# SEP00000AG.net
KiCad netlist of a schematic drawn in Altium Designer
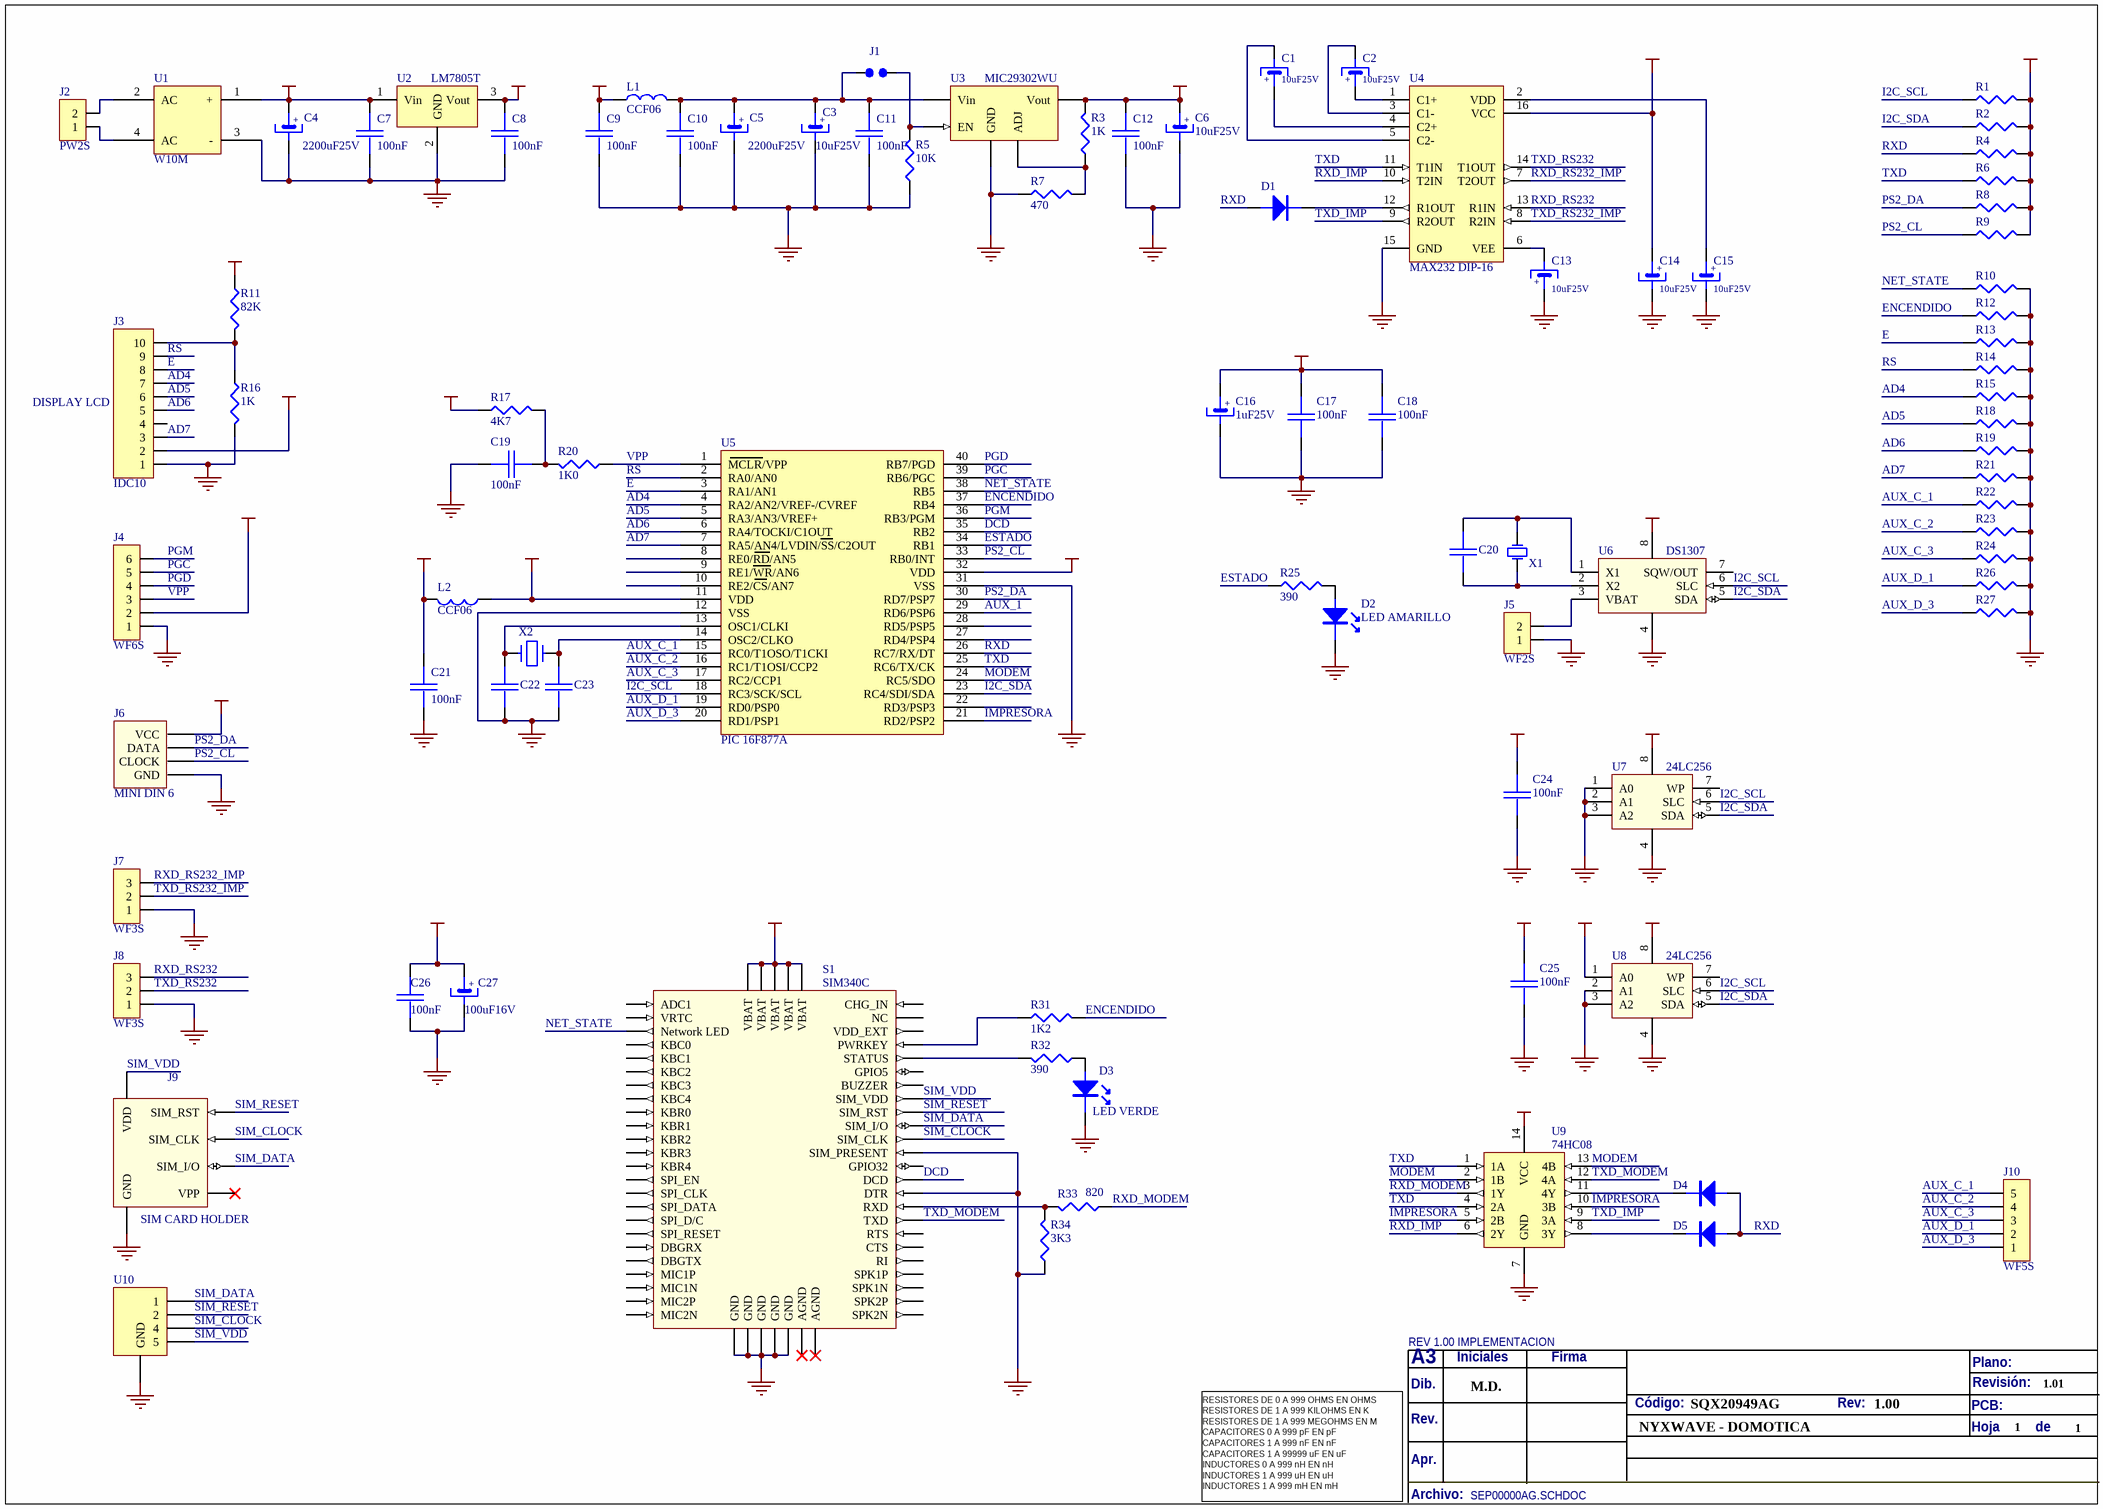
[diagram p0: SEP00000AG.SCHDOC]

(export (version "E")
  (design (tool "Eeschema 10.0.6"))
  (components
    (comp (ref "C1")
      (value "10uF25V")
      (footprint "CE 2.0/5.0")
      (description "CAPACITOR ELECTROLITICO RADIAL 5X11mm PASO 2mm 85ªC +/-20 25V 10uF")
      (libsource (lib "CAPACITORES ELECTROLITICOS") (part "10uF25V 5X11X2"))
    )
    (comp (ref "C2")
      (value "10uF25V")
      (footprint "CE 2.0/5.0")
      (description "CAPACITOR ELECTROLITICO RADIAL 5X11mm PASO 2mm 85ªC +/-20 25V 10uF")
      (libsource (lib "CAPACITORES ELECTROLITICOS") (part "10uF25V 5X11X2"))
    )
    (comp (ref "C3")
      (value "10uF25V")
      (footprint "CE 1.5/4.0")
      (description "CAPACITOR ELECTROLITICO RADIAL 5X7mm PASO 1.5mm 85ªC +/-20 25V 10uF")
      (libsource (lib "CAPACITORES ELECTROLITICOS") (part "10uF25V 4X7X1.5"))
    )
    (comp (ref "C4")
      (value "2200uF25V")
      (footprint "CE 5.0/12.5")
      (description "CAPACITOR ELECTROLITICO RADIAL 12.5X26 mm PASO 5 mm +/-20% 85ºC 25V 2200uF")
      (libsource (lib "CAPACITORES ELECTROLITICOS") (part "2200uF25V"))
    )
    (comp (ref "C5")
      (value "2200uF25V")
      (footprint "CE 5.0/12.5")
      (description "CAPACITOR ELECTROLITICO RADIAL 12.5X26 mm PASO 5 mm +/-20% 85ºC 25V 2200uF")
      (libsource (lib "CAPACITORES ELECTROLITICOS") (part "2200uF25V"))
    )
    (comp (ref "C6")
      (value "10uF25V")
      (footprint "CE 1.5/4.0")
      (description "CAPACITOR ELECTROLITICO RADIAL 5X7mm PASO 1.5mm 85ªC +/-20 25V 10uF")
      (libsource (lib "CAPACITORES ELECTROLITICOS") (part "10uF25V 4X7X1.5"))
    )
    (comp (ref "C7")
      (value "100nF")
      (footprint "0805")
      (description "CAPACITOR SMD 0805 X7R  50 V 100 nF")
      (libsource (lib "CAPACITORES SMD0805") (part "100n"))
    )
    (comp (ref "C8")
      (value "100nF")
      (footprint "0805")
      (description "CAPACITOR SMD 0805 X7R  50 V 100 nF")
      (libsource (lib "CAPACITORES SMD0805") (part "100n"))
    )
    (comp (ref "C9")
      (value "100nF")
      (footprint "0805")
      (description "CAPACITOR SMD 0805 X7R  50 V 100 nF")
      (libsource (lib "CAPACITORES SMD0805") (part "100n"))
    )
    (comp (ref "C10")
      (value "100nF")
      (footprint "0805")
      (description "CAPACITOR SMD 0805 X7R  50 V 100 nF")
      (libsource (lib "CAPACITORES SMD0805") (part "100n"))
    )
    (comp (ref "C11")
      (value "100nF")
      (footprint "0805")
      (description "CAPACITOR SMD 0805 X7R  50 V 100 nF")
      (libsource (lib "CAPACITORES SMD0805") (part "100n"))
    )
    (comp (ref "C12")
      (value "100nF")
      (footprint "0805")
      (description "CAPACITOR SMD 0805 X7R  50 V 100 nF")
      (libsource (lib "CAPACITORES SMD0805") (part "100n"))
    )
    (comp (ref "C13")
      (value "10uF25V")
      (footprint "CE 2.0/5.0")
      (description "CAPACITOR ELECTROLITICO RADIAL 5X11mm PASO 2mm 85ªC +/-20 25V 10uF")
      (libsource (lib "CAPACITORES ELECTROLITICOS") (part "10uF25V 5X11X2"))
    )
    (comp (ref "C14")
      (value "10uF25V")
      (footprint "CE 2.0/5.0")
      (description "CAPACITOR ELECTROLITICO RADIAL 5X11mm PASO 2mm 85ªC +/-20 25V 10uF")
      (libsource (lib "CAPACITORES ELECTROLITICOS") (part "10uF25V 5X11X2"))
    )
    (comp (ref "C15")
      (value "10uF25V")
      (footprint "CE 2.0/5.0")
      (description "CAPACITOR ELECTROLITICO RADIAL 5X11mm PASO 2mm 85ªC +/-20 25V 10uF")
      (libsource (lib "CAPACITORES ELECTROLITICOS") (part "10uF25V 5X11X2"))
    )
    (comp (ref "C16")
      (value "1uF25V")
      (footprint "CE 2.5/5.0")
      (description "CAP ELECT RAD 1.0UF 25V 5X11MM PASO 2MM 85ºC")
      (libsource (lib "CAPACITORES ELECTROLITICOS") (part "1uF25V"))
    )
    (comp (ref "C17")
      (value "100nF")
      (footprint "0805")
      (description "CAPACITOR SMD 0805 X7R  50 V 100 nF")
      (libsource (lib "CAPACITORES SMD0805") (part "100n"))
    )
    (comp (ref "C18")
      (value "100nF")
      (footprint "0805")
      (description "CAPACITOR SMD 0805 X7R  50 V 100 nF")
      (libsource (lib "CAPACITORES SMD0805") (part "100n"))
    )
    (comp (ref "C19")
      (value "100nF")
      (footprint "0805")
      (description "CAPACITOR SMD 0805 X7R  50 V 100 nF")
      (libsource (lib "CAPACITORES SMD0805") (part "100n"))
    )
    (comp (ref "C20")
      (value "15p")
      (footprint "CAP2.54")
      (description "CAPACITOR CERAMICO DISCO 2.54 mm  X7R  50V  15pF")
      (libsource (lib "CAPACITORES CERAMICO DISCO") (part "15p"))
    )
    (comp (ref "C21")
      (value "100nF")
      (footprint "0805")
      (description "CAPACITOR SMD 0805 X7R  50 V 100 nF")
      (libsource (lib "CAPACITORES SMD0805") (part "100n"))
    )
    (comp (ref "C22")
      (value "15p")
      (footprint "CAP2.54")
      (description "CAPACITOR CERAMICO DISCO 2.54 mm  X7R  50V  15pF")
      (libsource (lib "CAPACITORES CERAMICO DISCO") (part "15p"))
    )
    (comp (ref "C23")
      (value "15p")
      (footprint "CAP2.54")
      (description "CAPACITOR CERAMICO DISCO 2.54 mm  X7R  50V  15pF")
      (libsource (lib "CAPACITORES CERAMICO DISCO") (part "15p"))
    )
    (comp (ref "C24")
      (value "100nF")
      (footprint "0805")
      (description "CAPACITOR SMD 0805 X7R  50 V 100 nF")
      (libsource (lib "CAPACITORES SMD0805") (part "100n"))
    )
    (comp (ref "C25")
      (value "100nF")
      (footprint "0805")
      (description "CAPACITOR SMD 0805 X7R  50 V 100 nF")
      (libsource (lib "CAPACITORES SMD0805") (part "100n"))
    )
    (comp (ref "C26")
      (value "100nF")
      (footprint "0805")
      (description "CAPACITOR SMD 0805 X7R  50 V 100 nF")
      (libsource (lib "CAPACITORES SMD0805") (part "100n"))
    )
    (comp (ref "C27")
      (value "100uF16V")
      (footprint "CE 3.5/8.0")
      (description "CAP ELECT RADIAL 100UF 16V 6.3X12MM PASO 2.5MM 85ºC 20%")
      (libsource (lib "CAPACITORES ELECTROLITICOS") (part "100uF16V"))
    )
    (comp (ref "D1")
      (value "1N4148 DO-35")
      (footprint "DO-35_200")
      (description "1N4148 DO-35 DIODO")
      (libsource (lib "DIODOS") (part "1N4148 DO-35"))
    )
    (comp (ref "D2")
      (value "LED AMARILLO")
      (footprint "LED 3MM")
      (description "LED AMARILLO 3MM")
      (libsource (lib "DIODOS") (part "LED AMARILLO 3MM"))
    )
    (comp (ref "D3")
      (value "LED VERDE")
      (footprint "LED 3MM")
      (description "LED VERDE 3MM")
      (libsource (lib "DIODOS") (part "LED VERDE 3MM"))
    )
    (comp (ref "D4")
      (value "1N4148 DO-35")
      (footprint "DO-35_200")
      (description "1N4148 DO-35 DIODO")
      (libsource (lib "DIODOS") (part "1N4148 DO-35"))
    )
    (comp (ref "D5")
      (value "1N4148 DO-35")
      (footprint "DO-35_200")
      (description "1N4148 DO-35 DIODO")
      (libsource (lib "DIODOS") (part "1N4148 DO-35"))
    )
    (comp (ref "J1") (value "Jumper") (footprint "IDC2") (libsource (lib "CONECTORES") (part "Jumper")))
    (comp (ref "J2")
      (value "PW2S")
      (footprint "PW2S")
      (description "PW2S HEADER .156\" RECTO 2 VIAS")
      (libsource (lib "CONECTORES") (part "PW2S"))
    )
    (comp (ref "J3")
      (value "IDC10")
      (footprint "IDC10")
      (description "CONECTOR IDC HEMBRA PCB NO POLARIZADO PASO 2.54 mm RECTO 2X5 VIAS")
      (libsource (lib "CONECTORES") (part "IDC10"))
    )
    (comp (ref "J4")
      (value "WF6S")
      (footprint "WF6S")
      (description "WF6S CONECTOR MACHO PASO 2.54 MM  6 VIAS RECTO")
      (libsource (lib "CONECTORES") (part "WF6S"))
    )
    (comp (ref "J5")
      (value "WF2S")
      (footprint "WF2S")
      (description "WF2S HEADER .100\" RECTO 2 VIAS")
      (libsource (lib "CONECTORES") (part "WF2S"))
    )
    (comp (ref "J6")
      (value "MINI DIN 6")
      (footprint "MINI DIN PCB")
      (description "CONECTOR MINI DIN 6 PARA PCB")
      (libsource (lib "mini din") (part "CONECTOR MINI DIN 6"))
    )
    (comp (ref "J7")
      (value "WF3S")
      (footprint "WF3S")
      (description "WF3S HEADER .100\" RECTO 3 VIAS")
      (libsource (lib "CONECTORES") (part "WF3S"))
    )
    (comp (ref "J8")
      (value "WF3S")
      (footprint "WF3S")
      (description "WF3S HEADER .100\" RECTO 3 VIAS")
      (libsource (lib "CONECTORES") (part "WF3S"))
    )
    (comp (ref "J9")
      (value "SIM CARD HOLDER")
      (footprint "SIM CARD HOLDER")
      (description "ZOCALO PARA TARJETA DE MEMORIA SIM")
      (libsource (lib "CONECTORES") (part "SIM CARD HOLDER"))
    )
    (comp (ref "J10")
      (value "WF5S")
      (footprint "WF5S")
      (description "WF5S HEADER .100\" RECTO 5 VIAS")
      (libsource (lib "CONECTORES") (part "WF5S"))
    )
    (comp (ref "L1")
      (value "CCF06")
      (footprint "AXIAL10X4_300")
      (description "INDUCTOR CCF06")
      (libsource (lib "INDUCTORES") (part "CCF06"))
    )
    (comp (ref "L2")
      (value "CCF06")
      (footprint "AXIAL10X4_300")
      (description "INDUCTOR CCF06")
      (libsource (lib "INDUCTORES") (part "CCF06"))
    )
    (comp (ref "R1")
      (value "10K")
      (footprint "0805")
      (description "RESISTOR SMD0805 0.125 W 5%  10 K OHMS")
      (libsource (lib "RESISTORES SMD0805") (part "10K"))
    )
    (comp (ref "R2")
      (value "10K")
      (footprint "0805")
      (description "RESISTOR SMD0805 0.125 W 5%  10 K OHMS")
      (libsource (lib "RESISTORES SMD0805") (part "10K"))
    )
    (comp (ref "R3")
      (value "1K")
      (footprint "RES_MF1/2W_200")
      (description "RESISTOR METAL FILM 0.5 W 5% 1 K OHMS")
      (libsource (lib "RESISTORES METAL FILM MEDIO WATT") (part "1K"))
    )
    (comp (ref "R4")
      (value "100K")
      (footprint "0805")
      (description "RESISTOR SMD0805 0.125 W 5%  100 K OHMS")
      (libsource (lib "RESISTORES SMD0805") (part "100K"))
    )
    (comp (ref "R5")
      (value "10K")
      (footprint "0805")
      (description "RESISTOR SMD0805 0.125 W 5%  10 K OHMS")
      (libsource (lib "RESISTORES SMD0805") (part "10K"))
    )
    (comp (ref "R6")
      (value "100K")
      (footprint "0805")
      (description "RESISTOR SMD0805 0.125 W 5%  100 K OHMS")
      (libsource (lib "RESISTORES SMD0805") (part "100K"))
    )
    (comp (ref "R7")
      (value "470")
      (footprint "RES_MF1/2W_200")
      (description "RESISTOR METAL FILM 0.5 W 5% 470 OHMS")
      (libsource (lib "RESISTORES METAL FILM MEDIO WATT") (part "470"))
    )
    (comp (ref "R8")
      (value "5K6")
      (footprint "0805")
      (description "RESISTOR SMD0805 0.125 W 5%  5.6 K OHMS")
      (libsource (lib "RESISTORES SMD0805") (part "5K6"))
    )
    (comp (ref "R9")
      (value "5K6")
      (footprint "0805")
      (description "RESISTOR SMD0805 0.125 W 5%  5.6 K OHMS")
      (libsource (lib "RESISTORES SMD0805") (part "5K6"))
    )
    (comp (ref "R10")
      (value "5K6")
      (footprint "0805")
      (description "RESISTOR SMD0805 0.125 W 5%  5.6 K OHMS")
      (libsource (lib "RESISTORES SMD0805") (part "5K6"))
    )
    (comp (ref "R11")
      (value "82K")
      (footprint "RES_MF1/2W_200")
      (description "RESISTOR METAL FILM 0.5 W 5% 82 KILOHMS")
      (libsource (lib "RESISTORES METAL FILM MEDIO WATT") (part "82K"))
    )
    (comp (ref "R12")
      (value "5K6")
      (footprint "0805")
      (description "RESISTOR SMD0805 0.125 W 5%  5.6 K OHMS")
      (libsource (lib "RESISTORES SMD0805") (part "5K6"))
    )
    (comp (ref "R13")
      (value "5K6")
      (footprint "0805")
      (description "RESISTOR SMD0805 0.125 W 5%  5.6 K OHMS")
      (libsource (lib "RESISTORES SMD0805") (part "5K6"))
    )
    (comp (ref "R14")
      (value "5K6")
      (footprint "0805")
      (description "RESISTOR SMD0805 0.125 W 5%  5.6 K OHMS")
      (libsource (lib "RESISTORES SMD0805") (part "5K6"))
    )
    (comp (ref "R15")
      (value "5K6")
      (footprint "0805")
      (description "RESISTOR SMD0805 0.125 W 5%  5.6 K OHMS")
      (libsource (lib "RESISTORES SMD0805") (part "5K6"))
    )
    (comp (ref "R16")
      (value "1K")
      (footprint "RES_MF1/2W_200")
      (description "RESISTOR METAL FILM 0.5 W 5% 1 K OHMS")
      (libsource (lib "RESISTORES METAL FILM MEDIO WATT") (part "1K"))
    )
    (comp (ref "R17")
      (value "4K7")
      (footprint "RES_MF1/2W_200")
      (description "RESISTOR METAL FILM 0.5 W 5% 4.7 KILOHMS")
      (libsource (lib "RESISTORES METAL FILM MEDIO WATT") (part "4K7"))
    )
    (comp (ref "R18")
      (value "5K6")
      (footprint "0805")
      (description "RESISTOR SMD0805 0.125 W 5%  5.6 K OHMS")
      (libsource (lib "RESISTORES SMD0805") (part "5K6"))
    )
    (comp (ref "R19")
      (value "5K6")
      (footprint "0805")
      (description "RESISTOR SMD0805 0.125 W 5%  5.6 K OHMS")
      (libsource (lib "RESISTORES SMD0805") (part "5K6"))
    )
    (comp (ref "R20")
      (value "1K0")
      (footprint "0805")
      (description "RESISTOR SMD0805 0.125 W 5%  1 K OHMS")
      (libsource (lib "RESISTORES SMD0805") (part "1K0"))
    )
    (comp (ref "R21")
      (value "5K6")
      (footprint "0805")
      (description "RESISTOR SMD0805 0.125 W 5%  5.6 K OHMS")
      (libsource (lib "RESISTORES SMD0805") (part "5K6"))
    )
    (comp (ref "R22")
      (value "8K2")
      (footprint "0805")
      (description "RESISTOR SMD0805 0.125 W 5%  8.2 K OHMS")
      (libsource (lib "RESISTORES SMD0805") (part "8K2"))
    )
    (comp (ref "R23")
      (value "8K2")
      (footprint "0805")
      (description "RESISTOR SMD0805 0.125 W 5%  8.2 K OHMS")
      (libsource (lib "RESISTORES SMD0805") (part "8K2"))
    )
    (comp (ref "R24")
      (value "8K2")
      (footprint "0805")
      (description "RESISTOR SMD0805 0.125 W 5%  8.2 K OHMS")
      (libsource (lib "RESISTORES SMD0805") (part "8K2"))
    )
    (comp (ref "R25")
      (value "390")
      (footprint "RES_MF1/2W_200")
      (description "RESISTOR METAL FILM 0.5 W 5% 390 OHMS")
      (libsource (lib "RESISTORES METAL FILM MEDIO WATT") (part "390"))
    )
    (comp (ref "R26")
      (value "8K2")
      (footprint "0805")
      (description "RESISTOR SMD0805 0.125 W 5%  8.2 K OHMS")
      (libsource (lib "RESISTORES SMD0805") (part "8K2"))
    )
    (comp (ref "R27")
      (value "8K2")
      (footprint "0805")
      (description "RESISTOR SMD0805 0.125 W 5%  8.2 K OHMS")
      (libsource (lib "RESISTORES SMD0805") (part "8K2"))
    )
    (comp (ref "R31")
      (value "1K2")
      (footprint "0805")
      (description "RESISTOR SMD0805 0.125 W 5%  1.2 K OHMS")
      (libsource (lib "RESISTORES SMD0805") (part "1K2"))
    )
    (comp (ref "R32")
      (value "390")
      (footprint "RES_MF1/2W_200")
      (description "RESISTOR METAL FILM 0.5 W 5% 390 OHMS")
      (libsource (lib "RESISTORES METAL FILM MEDIO WATT") (part "390"))
    )
    (comp (ref "R33")
      (value "820")
      (footprint "RES_MF1/2W_200")
      (description "RESISTOR METAL FILM 0.5 W 5% 820 OHMS")
      (libsource (lib "RESISTORES METAL FILM MEDIO WATT") (part "820"))
    )
    (comp (ref "R34")
      (value "3K3")
      (footprint "RES_MF1/2W_200")
      (description "RESISTOR METAL FILM 0.5 W 5% 3.3 KILOHMS")
      (libsource (lib "RESISTORES METAL FILM MEDIO WATT") (part "3K3"))
    )
    (comp (ref "S1")
      (value "SIM340C")
      (footprint "SIM340C")
      (description "SIM340C QUAD-BAND GSM/GPRS GSM850MHz/EGSM900MHz/DCS18000MHz/PCS1900MHz")
      (libsource (lib "SUBCONJUNTOS") (part "SIM340C QUAD-BAND GSM/GPRS"))
    )
    (comp (ref "U1")
      (value "W10M")
      (footprint "CASE22")
      (description "W10M CASE22 CIRC INT RECTIFICADOR PUENTE 1000V 1A")
      (libsource (lib "CIRCUITOS INTEGRADOS DIP") (part "W10M"))
    )
    (comp (ref "U2")
      (value "LM7805T")
      (footprint "TO-220_1")
      (description "LM7805T TO-220 CIRC INT")
      (libsource (lib "CIRCUITOS INTEGRADOS DIP") (part "LM7805T"))
    )
    (comp (ref "U3")
      (value "MIC29302WU")
      (footprint "TO-220-5S")
      (description "MIC29302WU TO-220 (T) HIGH CURRENT LOW DROPOUT REGULATORS")
      (libsource (lib "CIRCUITOS INTEGRADOS DIP") (part "MIC29302WU"))
    )
    (comp (ref "U4")
      (value "MAX232 DIP-16")
      (footprint "DIP16")
      (description "MAX232 DIP-16 CIRCUITO INTEGRADO")
      (libsource (lib "Maxim Communication Transceiver") (part "MAX232 DIP-16"))
    )
    (comp (ref "U5")
      (value "PIC 16F877A")
      (footprint "DIP40")
      (description "PIC16F877A-I/P DIP-40 MICROCHIP")
      (libsource (lib "CIRCUITOS INTEGRADOS DIP") (part "PIC 16F877A"))
    )
    (comp (ref "U6")
      (value "DS1307")
      (footprint "DIP8")
      (description "64 X 8 SERIAL REAL TIME CLOCK")
      (libsource (lib "CIRCUITOS INTEGRADOS DIP") (part "DS1307"))
    )
    (comp (ref "U7")
      (value "24LC256")
      (footprint "DIP8")
      (description "256K I2C CMOS Serial EEPROM")
      (libsource (lib "CIRCUITOS INTEGRADOS DIP") (part "24LC256"))
    )
    (comp (ref "U8")
      (value "24LC256")
      (footprint "DIP8")
      (description "256K I2C CMOS Serial EEPROM")
      (libsource (lib "CIRCUITOS INTEGRADOS DIP") (part "24LC256"))
    )
    (comp (ref "U9")
      (value "74HC08")
      (footprint "DIP14")
      (description "74HC08 DIP-14 QUAD 2-INPUT AND GATE")
      (libsource (lib "CIRCUITOS INTEGRADOS DIP") (part "74HC08 DIP"))
    )
    (comp (ref "U10")
      (value "ESDA6V1W5")
      (footprint "SOT-323-5L")
      (description "ESDA6V1W5 ARRAY  FOR ESD PROTECTION")
      (libsource (lib "CIRCUITOS INTEGRADOS SMD") (part "ESDA6V1W5"))
    )
    (comp (ref "X1")
      (value "XL20M-UM5")
      (footprint "UM5")
      (description "XL20M-UM5 CRISTAL DE 20 MHZ 10ppm")
      (libsource (lib "CRISTALES") (part "XL20M-UM5"))
    )
    (comp (ref "X2")
      (value "20MHz")
      (footprint "UM5")
      (description "20.000 MHZ XL20M-UM5 10PPM CRISTAL")
      (libsource (lib "*") (part "CRYSTAL"))
    )
  )
  (nets
    (net (code "1") (name "+5V") (class "Default")
      (node (ref "C14") (pin "1") (pinfunction "1_1") (pintype "passive"))
      (node (ref "C21") (pin "2") (pintype "passive"))
      (node (ref "C24") (pin "2") (pintype "passive"))
      (node (ref "C25") (pin "2") (pintype "passive"))
      (node (ref "C8") (pin "2") (pintype "passive"))
      (node (ref "J3") (pin "2") (pinfunction "2_2") (pintype "passive"))
      (node (ref "J6") (pin "4") (pinfunction "VCC_4") (pintype "power_in"))
      (node (ref "L2") (pin "2") (pintype "passive"))
      (node (ref "R1") (pin "2") (pintype "passive"))
      (node (ref "R11") (pin "2") (pintype "passive"))
      (node (ref "R17") (pin "1") (pintype "passive"))
      (node (ref "R2") (pin "2") (pintype "passive"))
      (node (ref "R4") (pin "2") (pintype "passive"))
      (node (ref "R6") (pin "2") (pintype "passive"))
      (node (ref "R8") (pin "2") (pintype "passive"))
      (node (ref "R9") (pin "2") (pintype "passive"))
      (node (ref "U2") (pin "3") (pinfunction "Vout_3") (pintype "passive"))
      (node (ref "U4") (pin "16") (pinfunction "VCC_16") (pintype "power_in"))
      (node (ref "U6") (pin "8") (pinfunction "VCC_8") (pintype "power_in"))
      (node (ref "U7") (pin "8") (pinfunction "VCC_8") (pintype "power_in"))
      (node (ref "U8") (pin "1") (pinfunction "A0_1") (pintype "passive"))
      (node (ref "U8") (pin "8") (pinfunction "VCC_8") (pintype "power_in"))
      (node (ref "U9") (pin "14") (pinfunction "VCC_14") (pintype "power_in"))
    )
    (net (code "5") (name "/AD4") (class "Default")
      (node (ref "J3") (pin "7") (pinfunction "7_7") (pintype "passive"))
      (node (ref "R15") (pin "1") (pintype "passive"))
      (node (ref "U5") (pin "4") (pinfunction "RA2/AN2/VREF-/CVREF_4") (pintype "passive"))
    )
    (net (code "6") (name "/AD5") (class "Default")
      (node (ref "J3") (pin "6") (pinfunction "6_6") (pintype "passive"))
      (node (ref "R18") (pin "1") (pintype "passive"))
      (node (ref "U5") (pin "5") (pinfunction "RA3/AN3/VREF+_5") (pintype "passive"))
    )
    (net (code "7") (name "/AD6") (class "Default")
      (node (ref "J3") (pin "5") (pinfunction "5_5") (pintype "passive"))
      (node (ref "R19") (pin "1") (pintype "passive"))
      (node (ref "U5") (pin "6") (pinfunction "RA4/TOCKI/C1OUT_6") (pintype "passive"))
    )
    (net (code "8") (name "/AD7") (class "Default")
      (node (ref "J3") (pin "3") (pinfunction "3_3") (pintype "passive"))
      (node (ref "R21") (pin "1") (pintype "passive"))
      (node (ref "U5") (pin "7") (pinfunction "RA5/AN4/LVDIN/SS/C2OUT_7") (pintype "passive"))
    )
    (net (code "9") (name "/AUX_1") (class "Default")
      (node (ref "U5") (pin "29") (pinfunction "RD6/PSP6_29") (pintype "passive"))
    )
    (net (code "10") (name "/AUX_C_1") (class "Default")
      (node (ref "J10") (pin "5") (pinfunction "5_5") (pintype "passive"))
      (node (ref "R22") (pin "1") (pintype "passive"))
      (node (ref "U5") (pin "15") (pinfunction "RC0/T1OSO/T1CKI_15") (pintype "passive"))
    )
    (net (code "11") (name "/AUX_C_2") (class "Default")
      (node (ref "J10") (pin "4") (pinfunction "4_4") (pintype "passive"))
      (node (ref "R23") (pin "1") (pintype "passive"))
      (node (ref "U5") (pin "16") (pinfunction "RC1/T1OSI/CCP2_16") (pintype "passive"))
    )
    (net (code "12") (name "/AUX_C_3") (class "Default")
      (node (ref "J10") (pin "3") (pinfunction "3_3") (pintype "passive"))
      (node (ref "R24") (pin "1") (pintype "passive"))
      (node (ref "U5") (pin "17") (pinfunction "RC2/CCP1_17") (pintype "passive"))
    )
    (net (code "13") (name "/AUX_D_1") (class "Default")
      (node (ref "J10") (pin "2") (pinfunction "2_2") (pintype "passive"))
      (node (ref "R26") (pin "1") (pintype "passive"))
      (node (ref "U5") (pin "19") (pinfunction "RD0/PSP0_19") (pintype "passive"))
    )
    (net (code "14") (name "/AUX_D_3") (class "Default")
      (node (ref "J10") (pin "1") (pinfunction "1_1") (pintype "passive"))
      (node (ref "R27") (pin "1") (pintype "passive"))
      (node (ref "U5") (pin "20") (pinfunction "RD1/PSP1_20") (pintype "passive"))
    )
    (net (code "15") (name "/DCD") (class "Default")
      (node (ref "S1") (pin "37") (pinfunction "DCD_37") (pintype "output"))
      (node (ref "U5") (pin "35") (pinfunction "RB2_35") (pintype "passive"))
    )
    (net (code "16") (name "/E") (class "Default")
      (node (ref "J3") (pin "8") (pinfunction "8_8") (pintype "passive"))
      (node (ref "R13") (pin "1") (pintype "passive"))
      (node (ref "U5") (pin "3") (pinfunction "RA1/AN1_3") (pintype "passive"))
    )
    (net (code "17") (name "/ENCENDIDO") (class "Default")
      (node (ref "R12") (pin "1") (pintype "passive"))
      (node (ref "R31") (pin "2") (pintype "passive"))
      (node (ref "U5") (pin "37") (pinfunction "RB4_37") (pintype "passive"))
    )
    (net (code "18") (name "/ESTADO") (class "Default")
      (node (ref "R25") (pin "1") (pintype "passive"))
      (node (ref "U5") (pin "34") (pinfunction "RB1_34") (pintype "passive"))
    )
    (net (code "19") (name "/I2C_SCL") (class "Default")
      (node (ref "R1") (pin "1") (pintype "passive"))
      (node (ref "U5") (pin "18") (pinfunction "RC3/SCK/SCL_18") (pintype "passive"))
      (node (ref "U6") (pin "6") (pinfunction "SLC_6") (pintype "input"))
      (node (ref "U7") (pin "6") (pinfunction "SLC_6") (pintype "input"))
      (node (ref "U8") (pin "6") (pinfunction "SLC_6") (pintype "input"))
    )
    (net (code "20") (name "/I2C_SDA") (class "Default")
      (node (ref "R2") (pin "1") (pintype "passive"))
      (node (ref "U5") (pin "23") (pinfunction "RC4/SDI/SDA_23") (pintype "passive"))
      (node (ref "U6") (pin "5") (pinfunction "SDA_5") (pintype "bidirectional"))
      (node (ref "U7") (pin "5") (pinfunction "SDA_5") (pintype "bidirectional"))
      (node (ref "U8") (pin "5") (pinfunction "SDA_5") (pintype "bidirectional"))
    )
    (net (code "21") (name "/IMPRESORA") (class "Default")
      (node (ref "U5") (pin "21") (pinfunction "RD2/PSP2_21") (pintype "passive"))
      (node (ref "U9") (pin "10") (pinfunction "3B_10") (pintype "input"))
      (node (ref "U9") (pin "5") (pinfunction "2B_5") (pintype "input"))
    )
    (net (code "23") (name "/MODEM") (class "Default")
      (node (ref "U5") (pin "24") (pinfunction "RC5/SDO_24") (pintype "passive"))
      (node (ref "U9") (pin "13") (pinfunction "4B_13") (pintype "input"))
      (node (ref "U9") (pin "2") (pinfunction "1B_2") (pintype "input"))
    )
    (net (code "24") (name "/NET_STATE") (class "Default")
      (node (ref "R10") (pin "1") (pintype "passive"))
      (node (ref "S1") (pin "16") (pinfunction "Network_LED_16") (pintype "output"))
      (node (ref "U5") (pin "38") (pinfunction "RB5_38") (pintype "passive"))
    )
    (net (code "26") (name "/PGC") (class "Default")
      (node (ref "J4") (pin "5") (pinfunction "5_5") (pintype "passive"))
      (node (ref "U5") (pin "39") (pinfunction "RB6/PGC_39") (pintype "passive"))
    )
    (net (code "27") (name "/PGD") (class "Default")
      (node (ref "J4") (pin "4") (pinfunction "4_4") (pintype "passive"))
      (node (ref "U5") (pin "40") (pinfunction "RB7/PGD_40") (pintype "passive"))
    )
    (net (code "28") (name "/PGM") (class "Default")
      (node (ref "J4") (pin "6") (pinfunction "6_6") (pintype "passive"))
      (node (ref "U5") (pin "36") (pinfunction "RB3/PGM_36") (pintype "passive"))
    )
    (net (code "29") (name "/PS2_CL") (class "Default")
      (node (ref "J6") (pin "5") (pinfunction "CLOCK_5") (pintype "passive"))
      (node (ref "R9") (pin "1") (pintype "passive"))
      (node (ref "U5") (pin "33") (pinfunction "RB0/INT_33") (pintype "passive"))
    )
    (net (code "30") (name "/PS2_DA") (class "Default")
      (node (ref "J6") (pin "1") (pinfunction "DATA_1") (pintype "passive"))
      (node (ref "R8") (pin "1") (pintype "passive"))
      (node (ref "U5") (pin "30") (pinfunction "RD7/PSP7_30") (pintype "passive"))
    )
    (net (code "31") (name "/RS") (class "Default")
      (node (ref "J3") (pin "9") (pinfunction "9_9") (pintype "passive"))
      (node (ref "R14") (pin "1") (pintype "passive"))
      (node (ref "U5") (pin "2") (pinfunction "RA0/AN0_2") (pintype "passive"))
    )
    (net (code "32") (name "/RXD") (class "Default")
      (node (ref "D1") (pin "A") (pinfunction "A_A") (pintype "passive"))
      (node (ref "D4") (pin "A") (pinfunction "A_A") (pintype "passive"))
      (node (ref "D5") (pin "A") (pinfunction "A_A") (pintype "passive"))
      (node (ref "R4") (pin "1") (pintype "passive"))
      (node (ref "U5") (pin "26") (pinfunction "RC7/RX/DT_26") (pintype "passive"))
    )
    (net (code "33") (name "/RXD_IMP") (class "Default")
      (node (ref "U4") (pin "10") (pinfunction "T2IN_10") (pintype "input"))
      (node (ref "U9") (pin "6") (pinfunction "2Y_6") (pintype "output"))
    )
    (net (code "34") (name "/RXD_MODEM") (class "Default")
      (node (ref "R33") (pin "1") (pintype "passive"))
      (node (ref "U9") (pin "3") (pinfunction "1Y_3") (pintype "output"))
    )
    (net (code "35") (name "/RXD_RS232") (class "Default")
      (node (ref "J8") (pin "3") (pinfunction "3_3") (pintype "passive"))
      (node (ref "U4") (pin "13") (pinfunction "R1IN_13") (pintype "input"))
    )
    (net (code "36") (name "/RXD_RS232_IMP") (class "Default")
      (node (ref "J7") (pin "3") (pinfunction "3_3") (pintype "passive"))
      (node (ref "U4") (pin "7") (pinfunction "T2OUT_7") (pintype "output"))
    )
    (net (code "37") (name "/SIM_CLOCK") (class "Default")
      (node (ref "J9") (pin "3") (pinfunction "SIM_CLK_3") (pintype "input"))
      (node (ref "S1") (pin "31") (pinfunction "SIM_CLK_31") (pintype "output"))
      (node (ref "U10") (pin "4") (pinfunction "4_4") (pintype "passive"))
    )
    (net (code "38") (name "/SIM_DATA") (class "Default")
      (node (ref "J9") (pin "6") (pinfunction "SIM_I/O_6") (pintype "bidirectional"))
      (node (ref "S1") (pin "29") (pinfunction "SIM_I/O_29") (pintype "bidirectional"))
      (node (ref "U10") (pin "1") (pinfunction "1_1") (pintype "passive"))
    )
    (net (code "39") (name "/SIM_RESET") (class "Default")
      (node (ref "J9") (pin "2") (pinfunction "SIM_RST_2") (pintype "input"))
      (node (ref "S1") (pin "27") (pinfunction "SIM_RST_27") (pintype "output"))
      (node (ref "U10") (pin "2") (pinfunction "2_2") (pintype "passive"))
    )
    (net (code "40") (name "/SIM_VDD") (class "Default")
      (node (ref "J9") (pin "1") (pinfunction "VDD_1") (pintype "power_in"))
      (node (ref "S1") (pin "25") (pinfunction "SIM_VDD_25") (pintype "output"))
      (node (ref "U10") (pin "5") (pinfunction "5_5") (pintype "passive"))
    )
    (net (code "42") (name "/TXD") (class "Default")
      (node (ref "R6") (pin "1") (pintype "passive"))
      (node (ref "U4") (pin "11") (pinfunction "T1IN_11") (pintype "input"))
      (node (ref "U5") (pin "25") (pinfunction "RC6/TX/CK_25") (pintype "passive"))
      (node (ref "U9") (pin "1") (pinfunction "1A_1") (pintype "input"))
      (node (ref "U9") (pin "4") (pinfunction "2A_4") (pintype "input"))
    )
    (net (code "43") (name "/TXD_IMP") (class "Default")
      (node (ref "U4") (pin "9") (pinfunction "R2OUT_9") (pintype "output"))
      (node (ref "U9") (pin "9") (pinfunction "3A_9") (pintype "input"))
    )
    (net (code "44") (name "/TXD_MODEM") (class "Default")
      (node (ref "S1") (pin "43") (pinfunction "TXD_43") (pintype "output"))
      (node (ref "U9") (pin "12") (pinfunction "4A_12") (pintype "input"))
    )
    (net (code "45") (name "/TXD_RS232") (class "Default")
      (node (ref "J8") (pin "2") (pinfunction "2_2") (pintype "passive"))
      (node (ref "U4") (pin "14") (pinfunction "T1OUT_14") (pintype "output"))
    )
    (net (code "46") (name "/TXD_RS232_IMP") (class "Default")
      (node (ref "J7") (pin "2") (pinfunction "2_2") (pintype "passive"))
      (node (ref "U4") (pin "8") (pinfunction "R2IN_8") (pintype "input"))
    )
    (net (code "47") (name "/VPP") (class "Default")
      (node (ref "J4") (pin "3") (pinfunction "3_3") (pintype "passive"))
      (node (ref "R20") (pin "1") (pintype "passive"))
      (node (ref "U5") (pin "1") (pinfunction "MCLR/VPP_1") (pintype "passive"))
    )
    (net (code "48") (name "GND") (class "Default")
      (node (ref "C10") (pin "1") (pintype "passive"))
      (node (ref "C11") (pin "1") (pintype "passive"))
      (node (ref "C12") (pin "1") (pintype "passive"))
      (node (ref "C13") (pin "1") (pinfunction "1_1") (pintype "passive"))
      (node (ref "C14") (pin "2") (pinfunction "2_2") (pintype "passive"))
      (node (ref "C15") (pin "2") (pinfunction "2_2") (pintype "passive"))
      (node (ref "C16") (pin "2") (pinfunction "2_2") (pintype "passive"))
      (node (ref "C17") (pin "2") (pintype "passive"))
      (node (ref "C18") (pin "1") (pintype "passive"))
      (node (ref "C19") (pin "1") (pintype "passive"))
      (node (ref "C21") (pin "1") (pintype "passive"))
      (node (ref "C22") (pin "1") (pintype "passive"))
      (node (ref "C23") (pin "1") (pintype "passive"))
      (node (ref "C24") (pin "1") (pintype "passive"))
      (node (ref "C25") (pin "1") (pintype "passive"))
      (node (ref "C26") (pin "1") (pintype "passive"))
      (node (ref "C27") (pin "2") (pinfunction "2_2") (pintype "passive"))
      (node (ref "C3") (pin "2") (pinfunction "2_2") (pintype "passive"))
      (node (ref "C4") (pin "2") (pinfunction "2_2") (pintype "passive"))
      (node (ref "C5") (pin "2") (pinfunction "2_2") (pintype "passive"))
      (node (ref "C6") (pin "2") (pinfunction "2_2") (pintype "passive"))
      (node (ref "C7") (pin "1") (pintype "passive"))
      (node (ref "C8") (pin "1") (pintype "passive"))
      (node (ref "C9") (pin "1") (pintype "passive"))
      (node (ref "D2") (pin "K") (pinfunction "K_K") (pintype "passive"))
      (node (ref "D3") (pin "K") (pinfunction "K_K") (pintype "passive"))
      (node (ref "J3") (pin "1") (pinfunction "1_1") (pintype "passive"))
      (node (ref "J4") (pin "1") (pinfunction "1_1") (pintype "passive"))
      (node (ref "J5") (pin "1") (pinfunction "1_1") (pintype "passive"))
      (node (ref "J6") (pin "3") (pinfunction "GND_3") (pintype "passive"))
      (node (ref "J7") (pin "1") (pinfunction "1_1") (pintype "passive"))
      (node (ref "J8") (pin "1") (pinfunction "1_1") (pintype "passive"))
      (node (ref "J9") (pin "4") (pinfunction "GND_4") (pintype "passive"))
      (node (ref "R10") (pin "2") (pintype "passive"))
      (node (ref "R12") (pin "2") (pintype "passive"))
      (node (ref "R13") (pin "2") (pintype "passive"))
      (node (ref "R14") (pin "2") (pintype "passive"))
      (node (ref "R15") (pin "2") (pintype "passive"))
      (node (ref "R16") (pin "1") (pintype "passive"))
      (node (ref "R18") (pin "2") (pintype "passive"))
      (node (ref "R19") (pin "2") (pintype "passive"))
      (node (ref "R21") (pin "2") (pintype "passive"))
      (node (ref "R22") (pin "2") (pintype "passive"))
      (node (ref "R23") (pin "2") (pintype "passive"))
      (node (ref "R24") (pin "2") (pintype "passive"))
      (node (ref "R26") (pin "2") (pintype "passive"))
      (node (ref "R27") (pin "2") (pintype "passive"))
      (node (ref "R34") (pin "1") (pintype "passive"))
      (node (ref "R5") (pin "1") (pintype "passive"))
      (node (ref "R7") (pin "1") (pintype "passive"))
      (node (ref "S1") (pin "10") (pinfunction "GND_10") (pintype "passive"))
      (node (ref "S1") (pin "2") (pinfunction "GND_2") (pintype "passive"))
      (node (ref "S1") (pin "33") (pinfunction "SIM_PRESENT_33") (pintype "input"))
      (node (ref "S1") (pin "39") (pinfunction "DTR_39") (pintype "input"))
      (node (ref "S1") (pin "4") (pinfunction "GND_4") (pintype "passive"))
      (node (ref "S1") (pin "6") (pinfunction "GND_6") (pintype "passive"))
      (node (ref "S1") (pin "8") (pinfunction "GND_8") (pintype "passive"))
      (node (ref "U1") (pin "3") (pinfunction "-_3") (pintype "passive"))
      (node (ref "U10") (pin "3") (pinfunction "GND_3") (pintype "passive"))
      (node (ref "U2") (pin "2") (pinfunction "GND_2") (pintype "passive"))
      (node (ref "U3") (pin "3") (pinfunction "GND_3") (pintype "passive"))
      (node (ref "U4") (pin "15") (pinfunction "GND_15") (pintype "power_in"))
      (node (ref "U5") (pin "12") (pinfunction "VSS_12") (pintype "passive"))
      (node (ref "U5") (pin "31") (pinfunction "VSS_31") (pintype "passive"))
      (node (ref "U6") (pin "4") (pinfunction "VSS_4") (pintype "passive"))
      (node (ref "U7") (pin "1") (pinfunction "A0_1") (pintype "passive"))
      (node (ref "U7") (pin "2") (pinfunction "A1_2") (pintype "passive"))
      (node (ref "U7") (pin "3") (pinfunction "A2_3") (pintype "passive"))
      (node (ref "U7") (pin "4") (pinfunction "VSS_4") (pintype "passive"))
      (node (ref "U8") (pin "2") (pinfunction "A1_2") (pintype "passive"))
      (node (ref "U8") (pin "3") (pinfunction "A2_3") (pintype "passive"))
      (node (ref "U8") (pin "4") (pinfunction "VSS_4") (pintype "passive"))
      (node (ref "U9") (pin "7") (pinfunction "GND_7") (pintype "power_in"))
    )
    (net (code "49") (name "Net-(C19-Pad2)") (class "Default")
      (node (ref "C19") (pin "2") (pintype "passive"))
      (node (ref "R17") (pin "2") (pintype "passive"))
      (node (ref "R20") (pin "2") (pintype "passive"))
    )
    (net (code "50") (name "Net-(D2-PadA)") (class "Default")
      (node (ref "D2") (pin "A") (pinfunction "A_A") (pintype "passive"))
      (node (ref "R25") (pin "2") (pintype "passive"))
    )
    (net (code "51") (name "Net-(D3-PadA)") (class "Default")
      (node (ref "D3") (pin "A") (pinfunction "A_A") (pintype "passive"))
      (node (ref "R32") (pin "1") (pintype "passive"))
    )
    (net (code "52") (name "Net-(J2-Pad1)") (class "Default")
      (node (ref "J2") (pin "1") (pinfunction "1_1") (pintype "passive"))
      (node (ref "U1") (pin "4") (pinfunction "AC_4") (pintype "passive"))
    )
    (net (code "53") (name "Net-(J2-Pad2)") (class "Default")
      (node (ref "J2") (pin "2") (pinfunction "2_2") (pintype "passive"))
      (node (ref "U1") (pin "2") (pinfunction "AC_2") (pintype "passive"))
    )
    (net (code "54") (name "Net-(J3-Pad10)") (class "Default")
      (node (ref "J3") (pin "10") (pinfunction "10_10") (pintype "passive"))
      (node (ref "R11") (pin "1") (pintype "passive"))
      (node (ref "R16") (pin "2") (pintype "passive"))
    )
    (net (code "55") (name "Net-(S1-PWRKEY)") (class "Default")
      (node (ref "R31") (pin "1") (pintype "passive"))
      (node (ref "S1") (pin "17") (pinfunction "PWRKEY_17") (pintype "input"))
    )
    (net (code "56") (name "Net-(S1-RXD)") (class "Default")
      (node (ref "R33") (pin "2") (pintype "passive"))
      (node (ref "R34") (pin "2") (pintype "passive"))
      (node (ref "S1") (pin "41") (pinfunction "RXD_41") (pintype "input"))
    )
    (net (code "57") (name "Net-(S1-STATUS)") (class "Default")
      (node (ref "R32") (pin "2") (pintype "passive"))
      (node (ref "S1") (pin "19") (pinfunction "STATUS_19") (pintype "output"))
    )
    (net (code "58") (name "Net-(U3-ADJ)") (class "Default")
      (node (ref "R3") (pin "1") (pintype "passive"))
      (node (ref "R7") (pin "2") (pintype "passive"))
      (node (ref "U3") (pin "5") (pinfunction "ADJ_5") (pintype "passive"))
    )
    (net (code "59") (name "Net-(U3-EN)") (class "Default")
      (node (ref "J1") (pin "1") (pinfunction "1_1") (pintype "passive"))
      (node (ref "R5") (pin "2") (pintype "passive"))
      (node (ref "U3") (pin "1") (pinfunction "EN_1") (pintype "input"))
    )
    (net (code "60") (name "Net-(U3-Vin)") (class "Default")
      (node (ref "C10") (pin "2") (pintype "passive"))
      (node (ref "C11") (pin "2") (pintype "passive"))
      (node (ref "C3") (pin "1") (pinfunction "1_1") (pintype "passive"))
      (node (ref "C5") (pin "1") (pinfunction "1_1") (pintype "passive"))
      (node (ref "J1") (pin "2") (pinfunction "2_2") (pintype "passive"))
      (node (ref "L1") (pin "2") (pintype "passive"))
      (node (ref "U3") (pin "2") (pinfunction "Vin_2") (pintype "power_in"))
    )
    (net (code "61") (name "Net-(U4-C1+)") (class "Default")
      (node (ref "C2") (pin "1") (pinfunction "1_1") (pintype "passive"))
      (node (ref "U4") (pin "1") (pinfunction "C1+_1") (pintype "passive"))
    )
    (net (code "62") (name "Net-(U4-C1-)") (class "Default")
      (node (ref "C2") (pin "2") (pinfunction "2_2") (pintype "passive"))
      (node (ref "U4") (pin "3") (pinfunction "C1-_3") (pintype "passive"))
    )
    (net (code "63") (name "Net-(U4-C2+)") (class "Default")
      (node (ref "C1") (pin "1") (pinfunction "1_1") (pintype "passive"))
      (node (ref "U4") (pin "4") (pinfunction "C2+_4") (pintype "passive"))
    )
    (net (code "64") (name "Net-(U4-C2-)") (class "Default")
      (node (ref "C1") (pin "2") (pinfunction "2_2") (pintype "passive"))
      (node (ref "U4") (pin "5") (pinfunction "C2-_5") (pintype "passive"))
    )
    (net (code "65") (name "Net-(U4-R1OUT)") (class "Default")
      (node (ref "D1") (pin "K") (pinfunction "K_K") (pintype "passive"))
      (node (ref "U4") (pin "12") (pinfunction "R1OUT_12") (pintype "output"))
    )
    (net (code "66") (name "Net-(U4-VDD)") (class "Default")
      (node (ref "C15") (pin "1") (pinfunction "1_1") (pintype "passive"))
      (node (ref "U4") (pin "2") (pinfunction "VDD_2") (pintype "power_in"))
    )
    (net (code "67") (name "Net-(U4-VEE)") (class "Default")
      (node (ref "C13") (pin "2") (pinfunction "2_2") (pintype "passive"))
      (node (ref "U4") (pin "6") (pinfunction "VEE_6") (pintype "power_in"))
    )
    (net (code "68") (name "Net-(U5-OSC1{slash}CLKI)") (class "Default")
      (node (ref "C22") (pin "2") (pintype "passive"))
      (node (ref "U5") (pin "13") (pinfunction "OSC1/CLKI_13") (pintype "passive"))
      (node (ref "X2") (pin "2") (pintype "passive"))
    )
    (net (code "69") (name "Net-(U5-OSC2{slash}CLKO)") (class "Default")
      (node (ref "C23") (pin "2") (pintype "passive"))
      (node (ref "U5") (pin "14") (pinfunction "OSC2/CLKO_14") (pintype "passive"))
      (node (ref "X2") (pin "1") (pintype "passive"))
    )
    (net (code "70") (name "Net-(U6-VBAT)") (class "Default")
      (node (ref "J5") (pin "2") (pinfunction "2_2") (pintype "passive"))
      (node (ref "U6") (pin "3") (pinfunction "VBAT_3") (pintype "passive"))
    )
    (net (code "71") (name "Net-(U6-X1)") (class "Default")
      (node (ref "C20") (pin "2") (pintype "passive"))
      (node (ref "U6") (pin "1") (pinfunction "X1_1") (pintype "passive"))
      (node (ref "X1") (pin "2") (pinfunction "OSC2_2") (pintype "passive"))
    )
    (net (code "72") (name "Net-(U6-X2)") (class "Default")
      (node (ref "C20") (pin "1") (pintype "passive"))
      (node (ref "U6") (pin "2") (pinfunction "X2_2") (pintype "passive"))
      (node (ref "X1") (pin "1") (pinfunction "OSC1_1") (pintype "passive"))
    )
    (net (code "73") (name "Net-(U9-3Y)") (class "Default")
      (node (ref "D5") (pin "K") (pinfunction "K_K") (pintype "passive"))
      (node (ref "U9") (pin "8") (pinfunction "3Y_8") (pintype "output"))
    )
    (net (code "74") (name "Net-(U9-4Y)") (class "Default")
      (node (ref "D4") (pin "K") (pinfunction "K_K") (pintype "passive"))
      (node (ref "U9") (pin "11") (pinfunction "4Y_11") (pintype "output"))
    )
    (net (code "75") (name "VBAT") (class "Default")
      (node (ref "C12") (pin "2") (pintype "passive"))
      (node (ref "C26") (pin "2") (pintype "passive"))
      (node (ref "C27") (pin "1") (pinfunction "1_1") (pintype "passive"))
      (node (ref "C6") (pin "1") (pinfunction "1_1") (pintype "passive"))
      (node (ref "R3") (pin "2") (pintype "passive"))
      (node (ref "S1") (pin "1") (pinfunction "VBAT_1") (pintype "power_in"))
      (node (ref "S1") (pin "3") (pinfunction "VBAT_3") (pintype "power_in"))
      (node (ref "S1") (pin "5") (pinfunction "VBAT_5") (pintype "power_in"))
      (node (ref "S1") (pin "7") (pinfunction "VBAT_7") (pintype "power_in"))
      (node (ref "S1") (pin "9") (pinfunction "VBAT_9") (pintype "power_in"))
      (node (ref "U3") (pin "4") (pinfunction "Vout_4") (pintype "passive"))
    )
    (net (code "76") (name "VCC") (class "Default")
      (node (ref "C4") (pin "1") (pinfunction "1_1") (pintype "passive"))
      (node (ref "C7") (pin "2") (pintype "passive"))
      (node (ref "C9") (pin "2") (pintype "passive"))
      (node (ref "L1") (pin "1") (pintype "passive"))
      (node (ref "U1") (pin "1") (pinfunction "+_1") (pintype "passive"))
      (node (ref "U2") (pin "1") (pinfunction "Vin_1") (pintype "passive"))
    )
    (net (code "77") (name "VDD") (class "Default")
      (node (ref "C16") (pin "1") (pinfunction "1_1") (pintype "passive"))
      (node (ref "C17") (pin "1") (pintype "passive"))
      (node (ref "C18") (pin "2") (pintype "passive"))
      (node (ref "J4") (pin "2") (pinfunction "2_2") (pintype "passive"))
      (node (ref "L2") (pin "1") (pintype "passive"))
      (node (ref "U5") (pin "11") (pinfunction "VDD_11") (pintype "passive"))
      (node (ref "U5") (pin "32") (pinfunction "VDD_32") (pintype "passive"))
    )
    (net (code "78") (name "unconnected-(J3-Pad4)") (class "Default")
      (node (ref "J3") (pin "4") (pinfunction "4_4") (pintype "passive"))
    )
    (net (code "79") (name "unconnected-(J9-VPP-Pad5)") (class "Default")
      (node (ref "J9") (pin "5") (pinfunction "VPP_5") (pintype "passive+no_connect"))
    )
    (net (code "80") (name "unconnected-(S1-ADC1-Pad12)") (class "Default")
      (node (ref "S1") (pin "12") (pinfunction "ADC1_12") (pintype "input"))
    )
    (net (code "81") (name "unconnected-(S1-AGND-Pad51)") (class "Default")
      (node (ref "S1") (pin "51") (pinfunction "AGND_51") (pintype "passive+no_connect"))
    )
    (net (code "82") (name "unconnected-(S1-AGND-Pad52)") (class "Default")
      (node (ref "S1") (pin "52") (pinfunction "AGND_52") (pintype "passive+no_connect"))
    )
    (net (code "83") (name "unconnected-(S1-BUZZER-Pad23)") (class "Default")
      (node (ref "S1") (pin "23") (pinfunction "BUZZER_23") (pintype "output"))
    )
    (net (code "84") (name "unconnected-(S1-CHG_IN-Pad11)") (class "Default")
      (node (ref "S1") (pin "11") (pinfunction "CHG_IN_11") (pintype "input"))
    )
    (net (code "85") (name "unconnected-(S1-CTS-Pad47)") (class "Default")
      (node (ref "S1") (pin "47") (pinfunction "CTS_47") (pintype "output"))
    )
    (net (code "86") (name "unconnected-(S1-DBGRX-Pad48)") (class "Default")
      (node (ref "S1") (pin "48") (pinfunction "DBGRX_48") (pintype "input"))
    )
    (net (code "87") (name "unconnected-(S1-DBGTX-Pad50)") (class "Default")
      (node (ref "S1") (pin "50") (pinfunction "DBGTX_50") (pintype "output"))
    )
    (net (code "88") (name "unconnected-(S1-GPIO5-Pad21)") (class "Default")
      (node (ref "S1") (pin "21") (pinfunction "GPIO5_21") (pintype "bidirectional"))
    )
    (net (code "89") (name "unconnected-(S1-GPIO32-Pad35)") (class "Default")
      (node (ref "S1") (pin "35") (pinfunction "GPIO32_35") (pintype "bidirectional"))
    )
    (net (code "90") (name "unconnected-(S1-KBC0-Pad18)") (class "Default")
      (node (ref "S1") (pin "18") (pinfunction "KBC0_18") (pintype "output"))
    )
    (net (code "91") (name "unconnected-(S1-KBC1-Pad20)") (class "Default")
      (node (ref "S1") (pin "20") (pinfunction "KBC1_20") (pintype "output"))
    )
    (net (code "92") (name "unconnected-(S1-KBC2-Pad22)") (class "Default")
      (node (ref "S1") (pin "22") (pinfunction "KBC2_22") (pintype "output"))
    )
    (net (code "93") (name "unconnected-(S1-KBC3-Pad24)") (class "Default")
      (node (ref "S1") (pin "24") (pinfunction "KBC3_24") (pintype "output"))
    )
    (net (code "94") (name "unconnected-(S1-KBC4-Pad26)") (class "Default")
      (node (ref "S1") (pin "26") (pinfunction "KBC4_26") (pintype "output"))
    )
    (net (code "95") (name "unconnected-(S1-KBR0-Pad28)") (class "Default")
      (node (ref "S1") (pin "28") (pinfunction "KBR0_28") (pintype "input"))
    )
    (net (code "96") (name "unconnected-(S1-KBR1-Pad30)") (class "Default")
      (node (ref "S1") (pin "30") (pinfunction "KBR1_30") (pintype "input"))
    )
    (net (code "97") (name "unconnected-(S1-KBR2-Pad32)") (class "Default")
      (node (ref "S1") (pin "32") (pinfunction "KBR2_32") (pintype "input"))
    )
    (net (code "98") (name "unconnected-(S1-KBR3-Pad34)") (class "Default")
      (node (ref "S1") (pin "34") (pinfunction "KBR3_34") (pintype "input"))
    )
    (net (code "99") (name "unconnected-(S1-KBR4-Pad36)") (class "Default")
      (node (ref "S1") (pin "36") (pinfunction "KBR4_36") (pintype "input"))
    )
    (net (code "100") (name "unconnected-(S1-MIC1N-Pad56)") (class "Default")
      (node (ref "S1") (pin "56") (pinfunction "MIC1N_56") (pintype "input"))
    )
    (net (code "101") (name "unconnected-(S1-MIC1P-Pad54)") (class "Default")
      (node (ref "S1") (pin "54") (pinfunction "MIC1P_54") (pintype "input"))
    )
    (net (code "102") (name "unconnected-(S1-MIC2N-Pad60)") (class "Default")
      (node (ref "S1") (pin "60") (pinfunction "MIC2N_60") (pintype "input"))
    )
    (net (code "103") (name "unconnected-(S1-MIC2P-Pad58)") (class "Default")
      (node (ref "S1") (pin "58") (pinfunction "MIC2P_58") (pintype "input"))
    )
    (net (code "104") (name "unconnected-(S1-NC-Pad13)") (class "Default")
      (node (ref "S1") (pin "13") (pinfunction "NC_13") (pintype "passive"))
    )
    (net (code "105") (name "unconnected-(S1-RI-Pad49)") (class "Default")
      (node (ref "S1") (pin "49") (pinfunction "RI_49") (pintype "output"))
    )
    (net (code "106") (name "unconnected-(S1-RTS-Pad45)") (class "Default")
      (node (ref "S1") (pin "45") (pinfunction "RTS_45") (pintype "input"))
    )
    (net (code "107") (name "unconnected-(S1-SPI_CLK-Pad40)") (class "Default")
      (node (ref "S1") (pin "40") (pinfunction "SPI_CLK_40") (pintype "output"))
    )
    (net (code "108") (name "unconnected-(S1-SPI_DATA-Pad42)") (class "Default")
      (node (ref "S1") (pin "42") (pinfunction "SPI_DATA_42") (pintype "output"))
    )
    (net (code "109") (name "unconnected-(S1-SPI_D{slash}C-Pad44)") (class "Default")
      (node (ref "S1") (pin "44") (pinfunction "SPI_D/C_44") (pintype "output"))
    )
    (net (code "110") (name "unconnected-(S1-SPI_EN-Pad38)") (class "Default")
      (node (ref "S1") (pin "38") (pinfunction "SPI_EN_38") (pintype "output"))
    )
    (net (code "111") (name "unconnected-(S1-SPI_RESET-Pad46)") (class "Default")
      (node (ref "S1") (pin "46") (pinfunction "SPI_RESET_46") (pintype "output"))
    )
    (net (code "112") (name "unconnected-(S1-SPK1N-Pad55)") (class "Default")
      (node (ref "S1") (pin "55") (pinfunction "SPK1N_55") (pintype "output"))
    )
    (net (code "113") (name "unconnected-(S1-SPK1P-Pad53)") (class "Default")
      (node (ref "S1") (pin "53") (pinfunction "SPK1P_53") (pintype "output"))
    )
    (net (code "114") (name "unconnected-(S1-SPK2N-Pad59)") (class "Default")
      (node (ref "S1") (pin "59") (pinfunction "SPK2N_59") (pintype "output"))
    )
    (net (code "115") (name "unconnected-(S1-SPK2P-Pad57)") (class "Default")
      (node (ref "S1") (pin "57") (pinfunction "SPK2P_57") (pintype "output"))
    )
    (net (code "116") (name "unconnected-(S1-VDD_EXT-Pad15)") (class "Default")
      (node (ref "S1") (pin "15") (pinfunction "VDD_EXT_15") (pintype "output"))
    )
    (net (code "117") (name "unconnected-(S1-VRTC-Pad14)") (class "Default")
      (node (ref "S1") (pin "14") (pinfunction "VRTC_14") (pintype "input"))
    )
    (net (code "118") (name "unconnected-(U5-RD3{slash}PSP3-Pad22)") (class "Default")
      (node (ref "U5") (pin "22") (pinfunction "RD3/PSP3_22") (pintype "passive"))
    )
    (net (code "119") (name "unconnected-(U5-RD4{slash}PSP4-Pad27)") (class "Default")
      (node (ref "U5") (pin "27") (pinfunction "RD4/PSP4_27") (pintype "passive"))
    )
    (net (code "120") (name "unconnected-(U5-RD5{slash}PSP5-Pad28)") (class "Default")
      (node (ref "U5") (pin "28") (pinfunction "RD5/PSP5_28") (pintype "passive"))
    )
    (net (code "121") (name "unconnected-(U5-RE0{slash}RD{slash}AN5-Pad8)") (class "Default")
      (node (ref "U5") (pin "8") (pinfunction "RE0/RD/AN5_8") (pintype "passive"))
    )
    (net (code "122") (name "unconnected-(U5-RE1{slash}WR{slash}AN6-Pad9)") (class "Default")
      (node (ref "U5") (pin "9") (pinfunction "RE1/WR/AN6_9") (pintype "passive"))
    )
    (net (code "123") (name "unconnected-(U5-RE2{slash}CS{slash}AN7-Pad10)") (class "Default")
      (node (ref "U5") (pin "10") (pinfunction "RE2/CS/AN7_10") (pintype "passive"))
    )
    (net (code "124") (name "unconnected-(U6-SQW{slash}OUT-Pad7)") (class "Default")
      (node (ref "U6") (pin "7") (pinfunction "SQW/OUT_7") (pintype "passive"))
    )
    (net (code "125") (name "unconnected-(U7-WP-Pad7)") (class "Default")
      (node (ref "U7") (pin "7") (pinfunction "WP_7") (pintype "passive"))
    )
    (net (code "126") (name "unconnected-(U8-WP-Pad7)") (class "Default")
      (node (ref "U8") (pin "7") (pinfunction "WP_7") (pintype "passive"))
    )
  )
)
